# Ekogolf-board.net
KiCad netlist of a schematic drawn in EAGLE
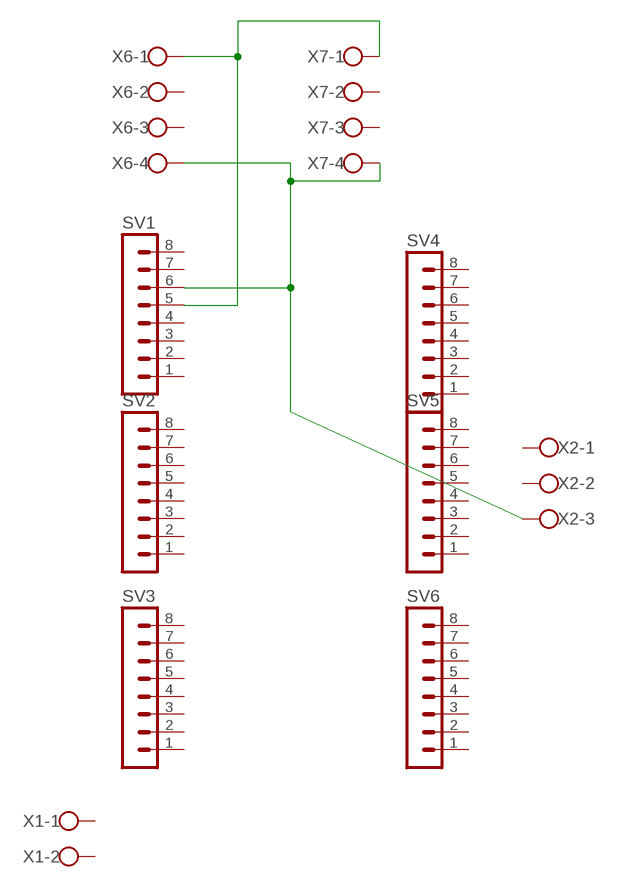
[diagram p0: schematic, sheet 1]

(export (version "E")
  (design (tool "Eeschema 10.0.6"))
  (components
    (comp (ref "SV1")
      (value "MA08-1")
      (footprint "eagle-import:MA08-1")
      (libsource (lib "eagle-import") (part "MA08-1"))
    )
    (comp (ref "SV2")
      (value "MA08-1")
      (footprint "eagle-import:MA08-1")
      (libsource (lib "eagle-import") (part "MA08-1"))
    )
    (comp (ref "SV3")
      (value "MA08-1")
      (footprint "eagle-import:MA08-1")
      (libsource (lib "eagle-import") (part "MA08-1"))
    )
    (comp (ref "SV4")
      (value "MA08-1")
      (footprint "eagle-import:MA08-1")
      (libsource (lib "eagle-import") (part "MA08-1"))
    )
    (comp (ref "SV5")
      (value "MA08-1")
      (footprint "eagle-import:MA08-1")
      (libsource (lib "eagle-import") (part "MA08-1"))
    )
    (comp (ref "SV6")
      (value "MA08-1")
      (footprint "eagle-import:MA08-1")
      (libsource (lib "eagle-import") (part "MA08-1"))
    )
    (comp (ref "X1")
      (value "W237-102")
      (footprint "eagle-import:W237-102")
      (fields (field (name "MPN") "237-102"))
      (libsource (lib "eagle-import") (part "W237-102"))
    )
    (comp (ref "X2")
      (value "W237-103")
      (footprint "eagle-import:W237-103")
      (fields (field (name "MPN") "237-103"))
      (libsource (lib "eagle-import") (part "W237-103"))
    )
    (comp (ref "X6")
      (value "W237-4")
      (footprint "eagle-import:W237-4")
      (libsource (lib "eagle-import") (part "W237-4"))
    )
    (comp (ref "X7")
      (value "W237-4")
      (footprint "eagle-import:W237-4")
      (libsource (lib "eagle-import") (part "W237-4"))
    )
  )
  (nets
    (net (code "1") (name "Net-(X2C-KL)") (class "Default")
      (node (ref "SV1") (pin "6") (pinfunction "6_6") (pintype "passive"))
      (node (ref "X2") (pin "3") (pinfunction "KL_3") (pintype "passive"))
      (node (ref "X6") (pin "4") (pinfunction "KL_4") (pintype "passive"))
      (node (ref "X7") (pin "4") (pinfunction "KL_4") (pintype "passive"))
    )
    (net (code "2") (name "Net-(X6A-KL)") (class "Default")
      (node (ref "SV1") (pin "5") (pinfunction "5_5") (pintype "passive"))
      (node (ref "X6") (pin "1") (pinfunction "KL_1") (pintype "passive"))
      (node (ref "X7") (pin "1") (pinfunction "KL_1") (pintype "passive"))
    )
    (net (code "3") (name "unconnected-(SV1-Pad1)") (class "Default")
      (node (ref "SV1") (pin "1") (pinfunction "1_1") (pintype "passive"))
    )
    (net (code "4") (name "unconnected-(SV1-Pad2)") (class "Default")
      (node (ref "SV1") (pin "2") (pinfunction "2_2") (pintype "passive"))
    )
    (net (code "5") (name "unconnected-(SV1-Pad3)") (class "Default")
      (node (ref "SV1") (pin "3") (pinfunction "3_3") (pintype "passive"))
    )
    (net (code "6") (name "unconnected-(SV1-Pad4)") (class "Default")
      (node (ref "SV1") (pin "4") (pinfunction "4_4") (pintype "passive"))
    )
    (net (code "7") (name "unconnected-(SV1-Pad7)") (class "Default")
      (node (ref "SV1") (pin "7") (pinfunction "7_7") (pintype "passive"))
    )
    (net (code "8") (name "unconnected-(SV1-Pad8)") (class "Default")
      (node (ref "SV1") (pin "8") (pinfunction "8_8") (pintype "passive"))
    )
    (net (code "9") (name "unconnected-(SV2-Pad1)") (class "Default")
      (node (ref "SV2") (pin "1") (pinfunction "1_1") (pintype "passive"))
    )
    (net (code "10") (name "unconnected-(SV2-Pad2)") (class "Default")
      (node (ref "SV2") (pin "2") (pinfunction "2_2") (pintype "passive"))
    )
    (net (code "11") (name "unconnected-(SV2-Pad3)") (class "Default")
      (node (ref "SV2") (pin "3") (pinfunction "3_3") (pintype "passive"))
    )
    (net (code "12") (name "unconnected-(SV2-Pad4)") (class "Default")
      (node (ref "SV2") (pin "4") (pinfunction "4_4") (pintype "passive"))
    )
    (net (code "13") (name "unconnected-(SV2-Pad5)") (class "Default")
      (node (ref "SV2") (pin "5") (pinfunction "5_5") (pintype "passive"))
    )
    (net (code "14") (name "unconnected-(SV2-Pad6)") (class "Default")
      (node (ref "SV2") (pin "6") (pinfunction "6_6") (pintype "passive"))
    )
    (net (code "15") (name "unconnected-(SV2-Pad7)") (class "Default")
      (node (ref "SV2") (pin "7") (pinfunction "7_7") (pintype "passive"))
    )
    (net (code "16") (name "unconnected-(SV2-Pad8)") (class "Default")
      (node (ref "SV2") (pin "8") (pinfunction "8_8") (pintype "passive"))
    )
    (net (code "17") (name "unconnected-(SV3-Pad1)") (class "Default")
      (node (ref "SV3") (pin "1") (pinfunction "1_1") (pintype "passive"))
    )
    (net (code "18") (name "unconnected-(SV3-Pad2)") (class "Default")
      (node (ref "SV3") (pin "2") (pinfunction "2_2") (pintype "passive"))
    )
    (net (code "19") (name "unconnected-(SV3-Pad3)") (class "Default")
      (node (ref "SV3") (pin "3") (pinfunction "3_3") (pintype "passive"))
    )
    (net (code "20") (name "unconnected-(SV3-Pad4)") (class "Default")
      (node (ref "SV3") (pin "4") (pinfunction "4_4") (pintype "passive"))
    )
    (net (code "21") (name "unconnected-(SV3-Pad5)") (class "Default")
      (node (ref "SV3") (pin "5") (pinfunction "5_5") (pintype "passive"))
    )
    (net (code "22") (name "unconnected-(SV3-Pad6)") (class "Default")
      (node (ref "SV3") (pin "6") (pinfunction "6_6") (pintype "passive"))
    )
    (net (code "23") (name "unconnected-(SV3-Pad7)") (class "Default")
      (node (ref "SV3") (pin "7") (pinfunction "7_7") (pintype "passive"))
    )
    (net (code "24") (name "unconnected-(SV3-Pad8)") (class "Default")
      (node (ref "SV3") (pin "8") (pinfunction "8_8") (pintype "passive"))
    )
    (net (code "25") (name "unconnected-(SV4-Pad1)") (class "Default")
      (node (ref "SV4") (pin "1") (pinfunction "1_1") (pintype "passive"))
    )
    (net (code "26") (name "unconnected-(SV4-Pad2)") (class "Default")
      (node (ref "SV4") (pin "2") (pinfunction "2_2") (pintype "passive"))
    )
    (net (code "27") (name "unconnected-(SV4-Pad3)") (class "Default")
      (node (ref "SV4") (pin "3") (pinfunction "3_3") (pintype "passive"))
    )
    (net (code "28") (name "unconnected-(SV4-Pad4)") (class "Default")
      (node (ref "SV4") (pin "4") (pinfunction "4_4") (pintype "passive"))
    )
    (net (code "29") (name "unconnected-(SV4-Pad5)") (class "Default")
      (node (ref "SV4") (pin "5") (pinfunction "5_5") (pintype "passive"))
    )
    (net (code "30") (name "unconnected-(SV4-Pad6)") (class "Default")
      (node (ref "SV4") (pin "6") (pinfunction "6_6") (pintype "passive"))
    )
    (net (code "31") (name "unconnected-(SV4-Pad7)") (class "Default")
      (node (ref "SV4") (pin "7") (pinfunction "7_7") (pintype "passive"))
    )
    (net (code "32") (name "unconnected-(SV4-Pad8)") (class "Default")
      (node (ref "SV4") (pin "8") (pinfunction "8_8") (pintype "passive"))
    )
    (net (code "33") (name "unconnected-(SV5-Pad1)") (class "Default")
      (node (ref "SV5") (pin "1") (pinfunction "1_1") (pintype "passive"))
    )
    (net (code "34") (name "unconnected-(SV5-Pad2)") (class "Default")
      (node (ref "SV5") (pin "2") (pinfunction "2_2") (pintype "passive"))
    )
    (net (code "35") (name "unconnected-(SV5-Pad3)") (class "Default")
      (node (ref "SV5") (pin "3") (pinfunction "3_3") (pintype "passive"))
    )
    (net (code "36") (name "unconnected-(SV5-Pad4)") (class "Default")
      (node (ref "SV5") (pin "4") (pinfunction "4_4") (pintype "passive"))
    )
    (net (code "37") (name "unconnected-(SV5-Pad5)") (class "Default")
      (node (ref "SV5") (pin "5") (pinfunction "5_5") (pintype "passive"))
    )
    (net (code "38") (name "unconnected-(SV5-Pad6)") (class "Default")
      (node (ref "SV5") (pin "6") (pinfunction "6_6") (pintype "passive"))
    )
    (net (code "39") (name "unconnected-(SV5-Pad7)") (class "Default")
      (node (ref "SV5") (pin "7") (pinfunction "7_7") (pintype "passive"))
    )
    (net (code "40") (name "unconnected-(SV5-Pad8)") (class "Default")
      (node (ref "SV5") (pin "8") (pinfunction "8_8") (pintype "passive"))
    )
    (net (code "41") (name "unconnected-(SV6-Pad1)") (class "Default")
      (node (ref "SV6") (pin "1") (pinfunction "1_1") (pintype "passive"))
    )
    (net (code "42") (name "unconnected-(SV6-Pad2)") (class "Default")
      (node (ref "SV6") (pin "2") (pinfunction "2_2") (pintype "passive"))
    )
    (net (code "43") (name "unconnected-(SV6-Pad3)") (class "Default")
      (node (ref "SV6") (pin "3") (pinfunction "3_3") (pintype "passive"))
    )
    (net (code "44") (name "unconnected-(SV6-Pad4)") (class "Default")
      (node (ref "SV6") (pin "4") (pinfunction "4_4") (pintype "passive"))
    )
    (net (code "45") (name "unconnected-(SV6-Pad5)") (class "Default")
      (node (ref "SV6") (pin "5") (pinfunction "5_5") (pintype "passive"))
    )
    (net (code "46") (name "unconnected-(SV6-Pad6)") (class "Default")
      (node (ref "SV6") (pin "6") (pinfunction "6_6") (pintype "passive"))
    )
    (net (code "47") (name "unconnected-(SV6-Pad7)") (class "Default")
      (node (ref "SV6") (pin "7") (pinfunction "7_7") (pintype "passive"))
    )
    (net (code "48") (name "unconnected-(SV6-Pad8)") (class "Default")
      (node (ref "SV6") (pin "8") (pinfunction "8_8") (pintype "passive"))
    )
    (net (code "49") (name "unconnected-(X1A-KL-Pad1)") (class "Default")
      (node (ref "X1") (pin "1") (pinfunction "KL_1") (pintype "passive"))
    )
    (net (code "50") (name "unconnected-(X1B-KL-Pad2)") (class "Default")
      (node (ref "X1") (pin "2") (pinfunction "KL_2") (pintype "passive"))
    )
    (net (code "51") (name "unconnected-(X2A-KL-Pad1)") (class "Default")
      (node (ref "X2") (pin "1") (pinfunction "KL_1") (pintype "passive"))
    )
    (net (code "52") (name "unconnected-(X2B-KL-Pad2)") (class "Default")
      (node (ref "X2") (pin "2") (pinfunction "KL_2") (pintype "passive"))
    )
    (net (code "53") (name "unconnected-(X6B-KL-Pad2)") (class "Default")
      (node (ref "X6") (pin "2") (pinfunction "KL_2") (pintype "passive"))
    )
    (net (code "54") (name "unconnected-(X6C-KL-Pad3)") (class "Default")
      (node (ref "X6") (pin "3") (pinfunction "KL_3") (pintype "passive"))
    )
    (net (code "55") (name "unconnected-(X7B-KL-Pad2)") (class "Default")
      (node (ref "X7") (pin "2") (pinfunction "KL_2") (pintype "passive"))
    )
    (net (code "56") (name "unconnected-(X7C-KL-Pad3)") (class "Default")
      (node (ref "X7") (pin "3") (pinfunction "KL_3") (pintype "passive"))
    )
  )
)
